# UNG_8088_EVB_LAN9252-SPI_LAN9252-2.net
KiCad netlist of a schematic drawn in Altium Designer
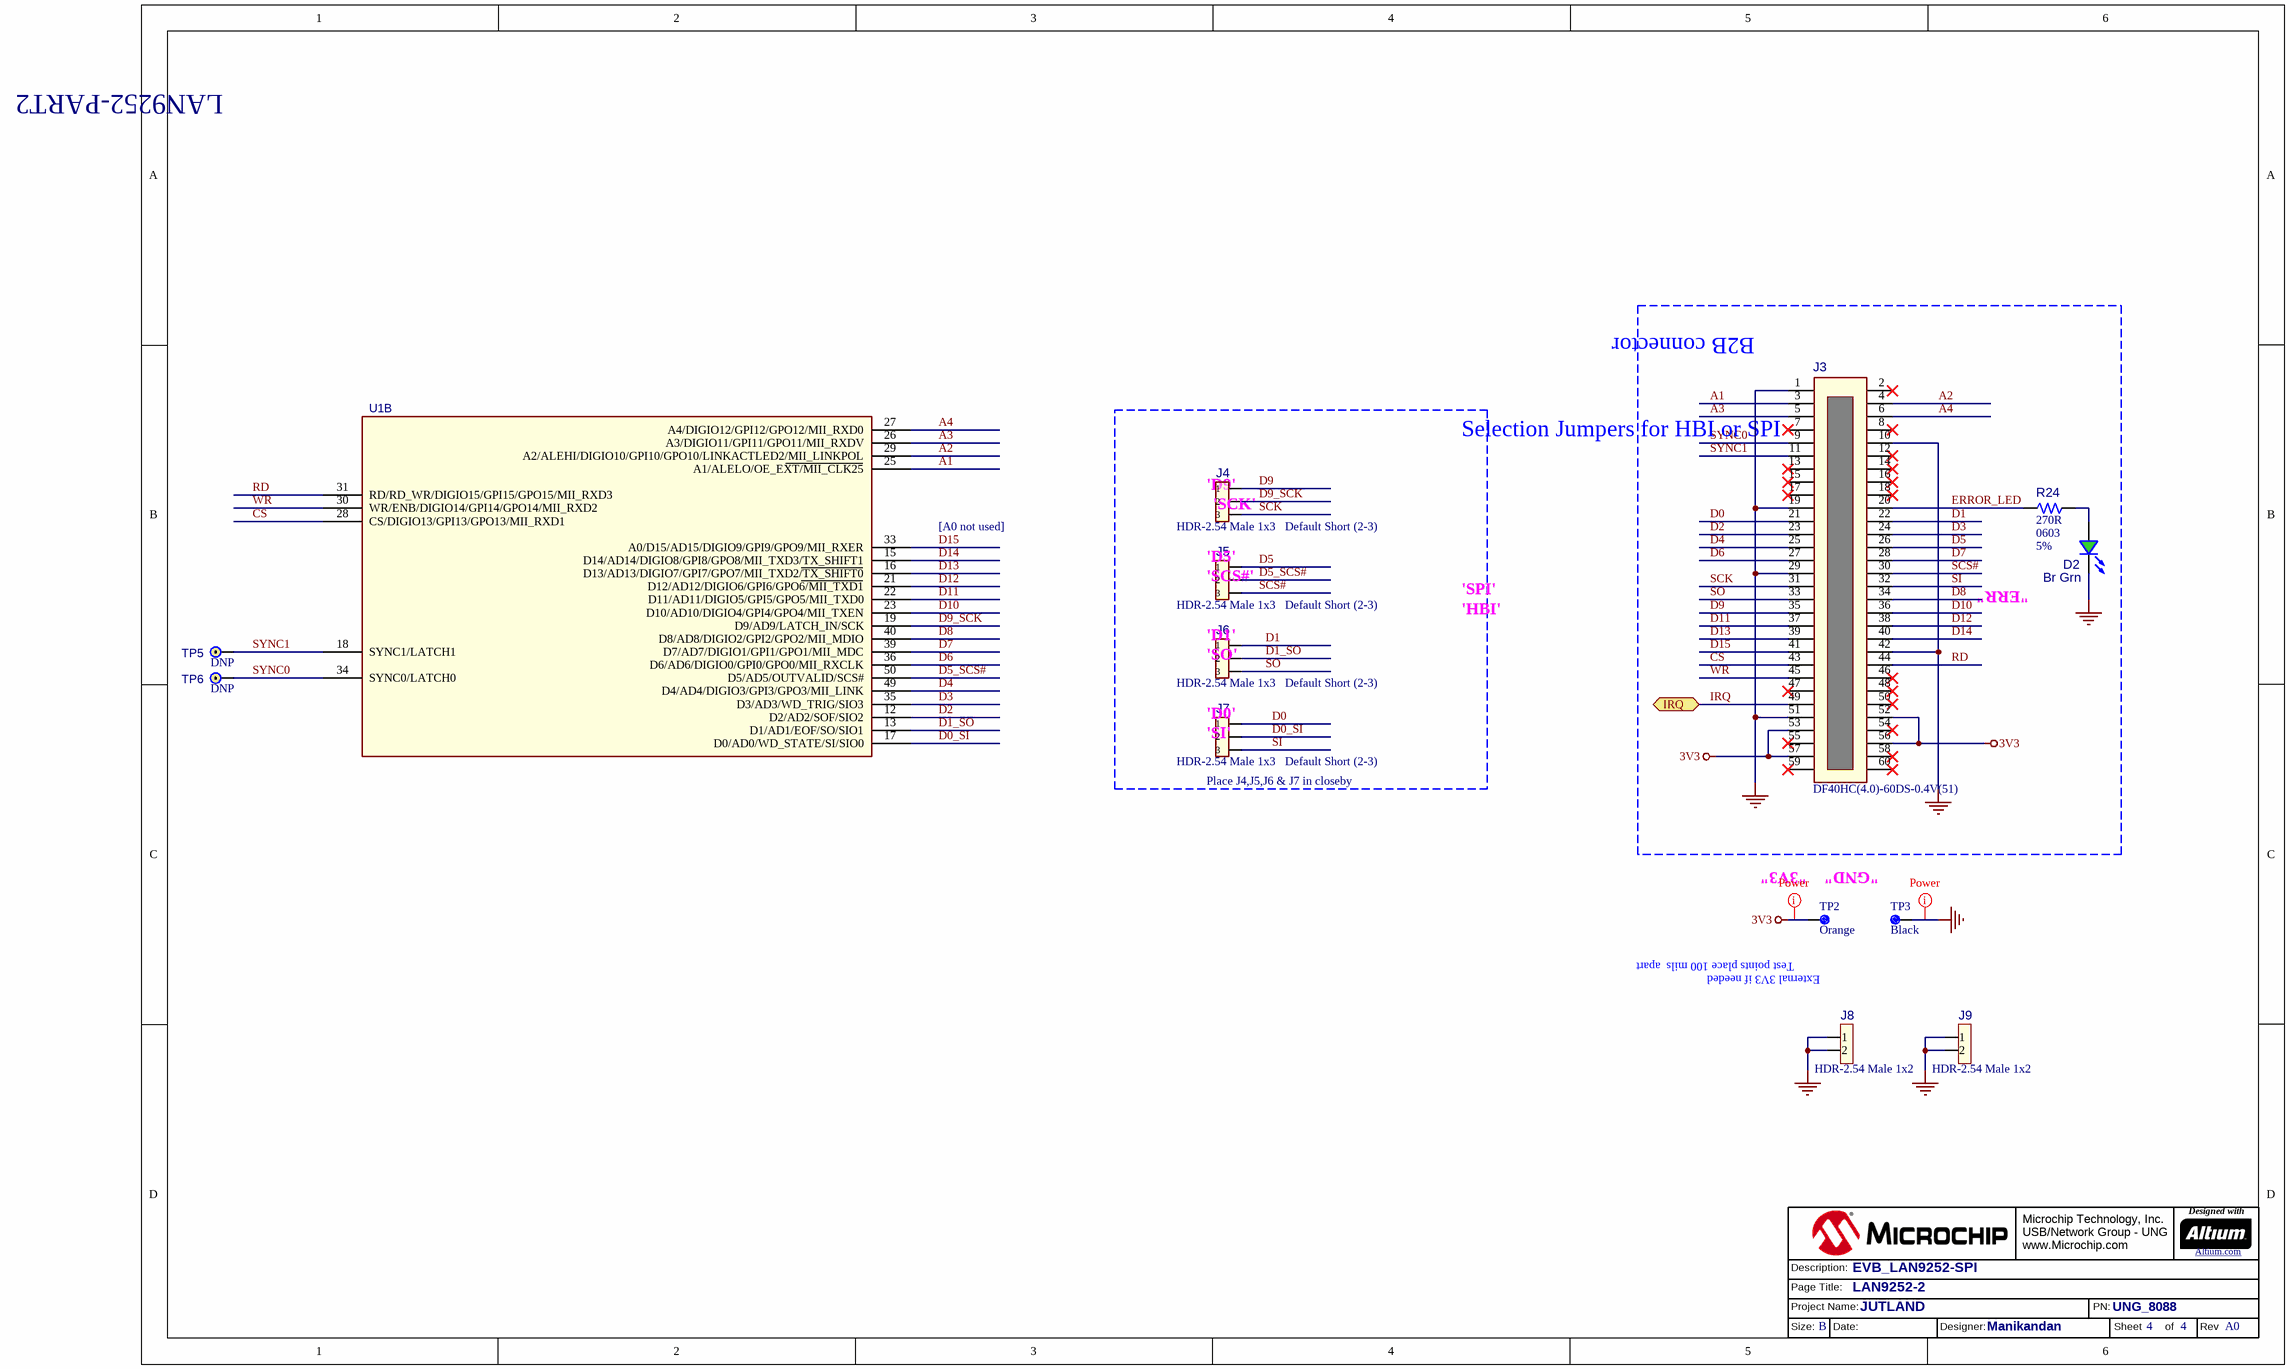
[diagram p0: UNG_8088_EVB_LAN9252-SPI_LAN9252-2.SchDoc]

(export (version "E")
  (design (tool "Eeschema 10.0.6"))
  (components
    (comp (ref "D2")
      (value "Br Grn")
      (footprint "LED_0603_GREEN")
      (description "LED, Bright Green, 0603")
      (fields (field (name "OWNER") "Jennifer Hancock"))
      (libsource (lib "UNG_DIODES") (part "LED, Bright Green, 0603"))
    )
    (comp (ref "J3")
      (value "DF40HC(4.0)-60DS-0.4V(51)")
      (footprint "CONN_DF40HC(4.0)-60DS-0.4V(51)")
      (description "CONN RCPT 60P 4MM DF40 HRS")
      (fields (field (name "Comment") "CONN DF40") (field (name "OWNER") "Manikandan"))
      (libsource (lib "UNG_CONNECTORS") (part "CONN RCPT 60P 4MM DF40 HRS"))
    )
    (comp (ref "J4")
      (value "HDR-2.54 Male 1x3")
      (footprint "HDR_M_2.54_1x3")
      (fields (field (name "Comment") "Header 1x3"))
      (libsource (lib "MCHP-CDB-Offline") (part "Header 1x3"))
    )
    (comp (ref "J5")
      (value "HDR-2.54 Male 1x3")
      (footprint "HDR_M_2.54_1x3")
      (fields (field (name "Comment") "Header 1x3"))
      (libsource (lib "MCHP-CDB-Offline") (part "Header 1x3"))
    )
    (comp (ref "J6")
      (value "HDR-2.54 Male 1x3")
      (footprint "HDR_M_2.54_1x3")
      (fields (field (name "Comment") "Header 1x3"))
      (libsource (lib "MCHP-CDB-Offline") (part "Header 1x3"))
    )
    (comp (ref "J7")
      (value "HDR-2.54 Male 1x3")
      (footprint "HDR_M_2.54_1x3")
      (fields (field (name "Comment") "Header 1x3"))
      (libsource (lib "MCHP-CDB-Offline") (part "Header 1x3"))
    )
    (comp (ref "J8")
      (value "HDR-2.54 Male 1x2")
      (footprint "HDR_M_2.54_1x2")
      (fields (field (name "Comment") "Header 1x2") (field (name "OWNER") "Randolph Sobrepena"))
      (libsource (lib "MCHP-CDB-Offline") (part "Header 1x2"))
    )
    (comp (ref "J9")
      (value "HDR-2.54 Male 1x2")
      (footprint "HDR_M_2.54_1x2")
      (fields (field (name "Comment") "Header 1x2") (field (name "OWNER") "Randolph Sobrepena"))
      (libsource (lib "MCHP-CDB-Offline") (part "Header 1x2"))
    )
    (comp (ref "R24")
      (value "270R")
      (footprint "RES_C_0603")
      (description "Resistor")
      (fields
        (field (name "PACKAGE") "0603")
        (field (name "TOLERANCE") "5%")
        (field (name "VOLTAGE") "75V")
        (field (name "POWER") "1/10W")
        (field (name "OWNER") "Bogdan P (M91398)")
      )
      (libsource (lib "MCHP-CDB") (part "Resistor"))
    )
    (comp (ref "TP2")
      (value "Mini Orange")
      (footprint "CON_TP_TH_V_ORANGE_KEC_5003")
      (description "TEST POINT PC MINI .040\"D ORANGE")
      (fields (field (name "COLOR") "Orange"))
      (libsource (lib "UNG_CONNECTORS") (part "TP 66R42 ORN"))
    )
    (comp (ref "TP3")
      (value "Mini Black")
      (footprint "CON_TP_TH_V_BLACK_KEC_5001")
      (description "TEST POINT PC MINI .040\"D BLACK")
      (fields (field (name "COLOR") "Black"))
      (libsource (lib "UNG_CONNECTORS") (part "TP 66R42 BLK"))
    )
    (comp (ref "TP5")
      (value "Jumper")
      (footprint "TP_PAD51D36")
      (description "Test Pad TH 51X36")
      (fields (field (name "MANUFACTURER PART NUMBER") "none") (field (name "POPULATED") "DNP"))
      (libsource (lib "UNG_CONNECTORS") (part "TEST PAD TH 51X36"))
    )
    (comp (ref "TP6")
      (value "Jumper")
      (footprint "TP_PAD51D36")
      (description "Test Pad TH 51X36")
      (fields (field (name "MANUFACTURER PART NUMBER") "none") (field (name "POPULATED") "DNP"))
      (libsource (lib "UNG_CONNECTORS") (part "TEST PAD TH 51X36"))
    )
    (comp (ref "U1")
      (value "~")
      (footprint "QFN-64_9x9_EP6SQ")
      (description "IC, 2/3-Port EtherCAT® Slave Controller, QFN64")
      (fields (field (name "OWNER") "Manikandan"))
      (libsource (lib "UNG_UNG") (part "LAN9252_QFN64"))
    )
  )
  (nets
    (net (code "1") (name "/A1") (class "Default")
      (node (ref "J3") (pin "3") (pinfunction "P3_3") (pintype "passive"))
      (node (ref "U1") (pin "25") (pinfunction "A1/ALELO/OE_EXT/MII_CLK25_25") (pintype "passive"))
    )
    (net (code "2") (name "/A2") (class "Default")
      (node (ref "J3") (pin "4") (pinfunction "P4_4") (pintype "passive"))
      (node (ref "U1") (pin "29") (pinfunction "A2/ALEHI/DIGIO10/GPI10/GPO10/LINKACTLED2/MII_LINKPOL_29") (pintype "passive"))
    )
    (net (code "3") (name "/A3") (class "Default")
      (node (ref "J3") (pin "5") (pinfunction "P5_5") (pintype "passive"))
      (node (ref "U1") (pin "26") (pinfunction "A3/DIGIO11/GPI11/GPO11/MII_RXDV_26") (pintype "passive"))
    )
    (net (code "4") (name "/A4") (class "Default")
      (node (ref "J3") (pin "6") (pinfunction "P6_6") (pintype "passive"))
      (node (ref "U1") (pin "27") (pinfunction "A4/DIGIO12/GPI12/GPO12/MII_RXD0_27") (pintype "passive"))
    )
    (net (code "5") (name "/CS") (class "Default")
      (node (ref "J3") (pin "43") (pinfunction "P43_43") (pintype "passive"))
      (node (ref "U1") (pin "28") (pinfunction "CS/DIGIO13/GPI13/GPO13/MII_RXD1_28") (pintype "passive"))
    )
    (net (code "6") (name "/D0") (class "Default")
      (node (ref "J3") (pin "21") (pinfunction "P21_21") (pintype "passive"))
      (node (ref "J7") (pin "1") (pinfunction "1_1") (pintype "passive"))
    )
    (net (code "7") (name "/D0_SI") (class "Default")
      (node (ref "J7") (pin "2") (pinfunction "2_2") (pintype "passive"))
      (node (ref "U1") (pin "17") (pinfunction "D0/AD0/WD_STATE/SI/SIO0_17") (pintype "passive"))
    )
    (net (code "8") (name "/D1") (class "Default")
      (node (ref "J3") (pin "22") (pinfunction "P22_22") (pintype "passive"))
      (node (ref "J6") (pin "1") (pinfunction "1_1") (pintype "passive"))
    )
    (net (code "9") (name "/D1_SO") (class "Default")
      (node (ref "J6") (pin "2") (pinfunction "2_2") (pintype "passive"))
      (node (ref "U1") (pin "13") (pinfunction "D1/AD1/EOF/SO/SIO1_13") (pintype "passive"))
    )
    (net (code "10") (name "/D2") (class "Default")
      (node (ref "J3") (pin "23") (pinfunction "P23_23") (pintype "passive"))
      (node (ref "U1") (pin "12") (pinfunction "D2/AD2/SOF/SIO2_12") (pintype "passive"))
    )
    (net (code "11") (name "/D3") (class "Default")
      (node (ref "J3") (pin "24") (pinfunction "P24_24") (pintype "passive"))
      (node (ref "U1") (pin "35") (pinfunction "D3/AD3/WD_TRIG/SIO3_35") (pintype "passive"))
    )
    (net (code "12") (name "/D4") (class "Default")
      (node (ref "J3") (pin "25") (pinfunction "P25_25") (pintype "passive"))
      (node (ref "U1") (pin "49") (pinfunction "D4/AD4/DIGIO3/GPI3/GPO3/MII_LINK_49") (pintype "passive"))
    )
    (net (code "13") (name "/D5") (class "Default")
      (node (ref "J3") (pin "26") (pinfunction "P26_26") (pintype "passive"))
      (node (ref "J5") (pin "1") (pinfunction "1_1") (pintype "passive"))
    )
    (net (code "14") (name "/D5_SCS#") (class "Default")
      (node (ref "J5") (pin "2") (pinfunction "2_2") (pintype "passive"))
      (node (ref "U1") (pin "50") (pinfunction "D5/AD5/OUTVALID/SCS#_50") (pintype "passive"))
    )
    (net (code "15") (name "/D6") (class "Default")
      (node (ref "J3") (pin "27") (pinfunction "P27_27") (pintype "passive"))
      (node (ref "U1") (pin "36") (pinfunction "D6/AD6/DIGIO0/GPI0/GPO0/MII_RXCLK_36") (pintype "passive"))
    )
    (net (code "16") (name "/D7") (class "Default")
      (node (ref "J3") (pin "28") (pinfunction "P28_28") (pintype "passive"))
      (node (ref "U1") (pin "39") (pinfunction "D7/AD7/DIGIO1/GPI1/GPO1/MII_MDC_39") (pintype "passive"))
    )
    (net (code "17") (name "/D8") (class "Default")
      (node (ref "J3") (pin "34") (pinfunction "P34_34") (pintype "passive"))
      (node (ref "U1") (pin "40") (pinfunction "D8/AD8/DIGIO2/GPI2/GPO2/MII_MDIO_40") (pintype "passive"))
    )
    (net (code "18") (name "/D9") (class "Default")
      (node (ref "J3") (pin "35") (pinfunction "P35_35") (pintype "passive"))
      (node (ref "J4") (pin "1") (pinfunction "1_1") (pintype "passive"))
    )
    (net (code "19") (name "/D9_SCK") (class "Default")
      (node (ref "J4") (pin "2") (pinfunction "2_2") (pintype "passive"))
      (node (ref "U1") (pin "19") (pinfunction "D9/AD9/LATCH_IN/SCK_19") (pintype "passive"))
    )
    (net (code "20") (name "/D10") (class "Default")
      (node (ref "J3") (pin "36") (pinfunction "P36_36") (pintype "passive"))
      (node (ref "U1") (pin "23") (pinfunction "D10/AD10/DIGIO4/GPI4/GPO4/MII_TXEN_23") (pintype "passive"))
    )
    (net (code "21") (name "/D11") (class "Default")
      (node (ref "J3") (pin "37") (pinfunction "P37_37") (pintype "passive"))
      (node (ref "U1") (pin "22") (pinfunction "D11/AD11/DIGIO5/GPI5/GPO5/MII_TXD0_22") (pintype "passive"))
    )
    (net (code "22") (name "/D12") (class "Default")
      (node (ref "J3") (pin "38") (pinfunction "P38_38") (pintype "passive"))
      (node (ref "U1") (pin "21") (pinfunction "D12/AD12/DIGIO6/GPI6/GPO6/MII_TXD1_21") (pintype "passive"))
    )
    (net (code "23") (name "/D13") (class "Default")
      (node (ref "J3") (pin "39") (pinfunction "P39_39") (pintype "passive"))
      (node (ref "U1") (pin "16") (pinfunction "D13/AD13/DIGIO7/GPI7/GPO7/MII_TXD2/TX_SHIFT0_16") (pintype "passive"))
    )
    (net (code "24") (name "/D14") (class "Default")
      (node (ref "J3") (pin "40") (pinfunction "P40_40") (pintype "passive"))
      (node (ref "U1") (pin "15") (pinfunction "D14/AD14/DIGIO8/GPI8/GPO8/MII_TXD3/TX_SHIFT1_15") (pintype "passive"))
    )
    (net (code "25") (name "/D15") (class "Default")
      (node (ref "J3") (pin "41") (pinfunction "P41_41") (pintype "passive"))
      (node (ref "U1") (pin "33") (pinfunction "A0/D15/AD15/DIGIO9/GPI9/GPO9/MII_RXER_33") (pintype "passive"))
    )
    (net (code "26") (name "/ERROR_LED") (class "Default")
      (node (ref "J3") (pin "20") (pinfunction "P20_20") (pintype "passive"))
      (node (ref "R24") (pin "2") (pinfunction "2_2") (pintype "passive"))
    )
    (net (code "27") (name "/IRQ") (class "Default")
      (node (ref "J3") (pin "49") (pinfunction "P49_49") (pintype "passive"))
    )
    (net (code "28") (name "/RD") (class "Default")
      (node (ref "J3") (pin "44") (pinfunction "P44_44") (pintype "passive"))
      (node (ref "U1") (pin "31") (pinfunction "RD/RD_WR/DIGIO15/GPI15/GPO15/MII_RXD3_31") (pintype "passive"))
    )
    (net (code "29") (name "/SCK") (class "Default")
      (node (ref "J3") (pin "31") (pinfunction "P31_31") (pintype "passive"))
      (node (ref "J4") (pin "3") (pinfunction "3_3") (pintype "passive"))
    )
    (net (code "30") (name "/SCS#") (class "Default")
      (node (ref "J3") (pin "30") (pinfunction "P30_30") (pintype "passive"))
      (node (ref "J5") (pin "3") (pinfunction "3_3") (pintype "passive"))
    )
    (net (code "31") (name "/SI") (class "Default")
      (node (ref "J3") (pin "32") (pinfunction "P32_32") (pintype "passive"))
      (node (ref "J7") (pin "3") (pinfunction "3_3") (pintype "passive"))
    )
    (net (code "32") (name "/SO") (class "Default")
      (node (ref "J3") (pin "33") (pinfunction "P33_33") (pintype "passive"))
      (node (ref "J6") (pin "3") (pinfunction "3_3") (pintype "passive"))
    )
    (net (code "33") (name "/SYNC0") (class "Default")
      (node (ref "J3") (pin "9") (pinfunction "P9_9") (pintype "passive"))
      (node (ref "TP6") (pin "1") (pinfunction "P1_1") (pintype "passive"))
      (node (ref "U1") (pin "34") (pinfunction "SYNC0/LATCH0_34") (pintype "passive"))
    )
    (net (code "34") (name "/SYNC1") (class "Default")
      (node (ref "J3") (pin "11") (pinfunction "P11_11") (pintype "passive"))
      (node (ref "TP5") (pin "1") (pinfunction "P1_1") (pintype "passive"))
      (node (ref "U1") (pin "18") (pinfunction "SYNC1/LATCH1_18") (pintype "passive"))
    )
    (net (code "35") (name "/WR") (class "Default")
      (node (ref "J3") (pin "45") (pinfunction "P45_45") (pintype "passive"))
      (node (ref "U1") (pin "30") (pinfunction "WR/ENB/DIGIO14/GPI14/GPO14/MII_RXD2_30") (pintype "passive"))
    )
    (net (code "36") (name "3V3") (class "Default")
      (node (ref "J3") (pin "52") (pinfunction "P52_52") (pintype "passive"))
      (node (ref "J3") (pin "53") (pinfunction "P53_53") (pintype "passive"))
      (node (ref "J3") (pin "56") (pinfunction "P56_56") (pintype "passive"))
      (node (ref "J3") (pin "57") (pinfunction "P57_57") (pintype "passive"))
      (node (ref "TP2") (pin "1") (pinfunction "1_1") (pintype "passive"))
    )
    (net (code "37") (name "GND") (class "Default")
      (node (ref "D2") (pin "2") (pinfunction "K_2") (pintype "passive"))
      (node (ref "J3") (pin "1") (pinfunction "P1_1") (pintype "passive"))
      (node (ref "J3") (pin "10") (pinfunction "P10_10") (pintype "passive"))
      (node (ref "J3") (pin "19") (pinfunction "P19_19") (pintype "passive"))
      (node (ref "J3") (pin "29") (pinfunction "P29_29") (pintype "passive"))
      (node (ref "J3") (pin "42") (pinfunction "P42_42") (pintype "passive"))
      (node (ref "J3") (pin "51") (pinfunction "P51_51") (pintype "passive"))
      (node (ref "J8") (pin "1") (pinfunction "1_1") (pintype "passive"))
      (node (ref "J8") (pin "2") (pinfunction "2_2") (pintype "passive"))
      (node (ref "J9") (pin "1") (pinfunction "1_1") (pintype "passive"))
      (node (ref "J9") (pin "2") (pinfunction "2_2") (pintype "passive"))
      (node (ref "TP3") (pin "1") (pinfunction "1_1") (pintype "passive"))
    )
    (net (code "38") (name "Net-(D2-A)") (class "Default")
      (node (ref "D2") (pin "1") (pinfunction "A_1") (pintype "passive"))
      (node (ref "R24") (pin "1") (pinfunction "1_1") (pintype "passive"))
    )
    (net (code "39") (name "unconnected-(J3-P2-Pad2)") (class "Default")
      (node (ref "J3") (pin "2") (pinfunction "P2_2") (pintype "passive+no_connect"))
    )
    (net (code "40") (name "unconnected-(J3-P7-Pad7)") (class "Default")
      (node (ref "J3") (pin "7") (pinfunction "P7_7") (pintype "passive+no_connect"))
    )
    (net (code "41") (name "unconnected-(J3-P8-Pad8)") (class "Default")
      (node (ref "J3") (pin "8") (pinfunction "P8_8") (pintype "passive+no_connect"))
    )
    (net (code "42") (name "unconnected-(J3-P12-Pad12)") (class "Default")
      (node (ref "J3") (pin "12") (pinfunction "P12_12") (pintype "passive+no_connect"))
    )
    (net (code "43") (name "unconnected-(J3-P13-Pad13)") (class "Default")
      (node (ref "J3") (pin "13") (pinfunction "P13_13") (pintype "passive+no_connect"))
    )
    (net (code "44") (name "unconnected-(J3-P14-Pad14)") (class "Default")
      (node (ref "J3") (pin "14") (pinfunction "P14_14") (pintype "passive+no_connect"))
    )
    (net (code "45") (name "unconnected-(J3-P15-Pad15)") (class "Default")
      (node (ref "J3") (pin "15") (pinfunction "P15_15") (pintype "passive+no_connect"))
    )
    (net (code "46") (name "unconnected-(J3-P16-Pad16)") (class "Default")
      (node (ref "J3") (pin "16") (pinfunction "P16_16") (pintype "passive+no_connect"))
    )
    (net (code "47") (name "unconnected-(J3-P17-Pad17)") (class "Default")
      (node (ref "J3") (pin "17") (pinfunction "P17_17") (pintype "passive+no_connect"))
    )
    (net (code "48") (name "unconnected-(J3-P18-Pad18)") (class "Default")
      (node (ref "J3") (pin "18") (pinfunction "P18_18") (pintype "passive+no_connect"))
    )
    (net (code "49") (name "unconnected-(J3-P46-Pad46)") (class "Default")
      (node (ref "J3") (pin "46") (pinfunction "P46_46") (pintype "passive+no_connect"))
    )
    (net (code "50") (name "unconnected-(J3-P47-Pad47)") (class "Default")
      (node (ref "J3") (pin "47") (pinfunction "P47_47") (pintype "passive+no_connect"))
    )
    (net (code "51") (name "unconnected-(J3-P48-Pad48)") (class "Default")
      (node (ref "J3") (pin "48") (pinfunction "P48_48") (pintype "passive+no_connect"))
    )
    (net (code "52") (name "unconnected-(J3-P50-Pad50)") (class "Default")
      (node (ref "J3") (pin "50") (pinfunction "P50_50") (pintype "passive+no_connect"))
    )
    (net (code "53") (name "unconnected-(J3-P54-Pad54)") (class "Default")
      (node (ref "J3") (pin "54") (pinfunction "P54_54") (pintype "passive+no_connect"))
    )
    (net (code "54") (name "unconnected-(J3-P55-Pad55)") (class "Default")
      (node (ref "J3") (pin "55") (pinfunction "P55_55") (pintype "passive+no_connect"))
    )
    (net (code "55") (name "unconnected-(J3-P58-Pad58)") (class "Default")
      (node (ref "J3") (pin "58") (pinfunction "P58_58") (pintype "passive+no_connect"))
    )
    (net (code "56") (name "unconnected-(J3-P59-Pad59)") (class "Default")
      (node (ref "J3") (pin "59") (pinfunction "P59_59") (pintype "passive+no_connect"))
    )
    (net (code "57") (name "unconnected-(J3-P60-Pad60)") (class "Default")
      (node (ref "J3") (pin "60") (pinfunction "P60_60") (pintype "passive+no_connect"))
    )
  )
)
